# Top.net
KiCad netlist of a schematic drawn in Altium Designer
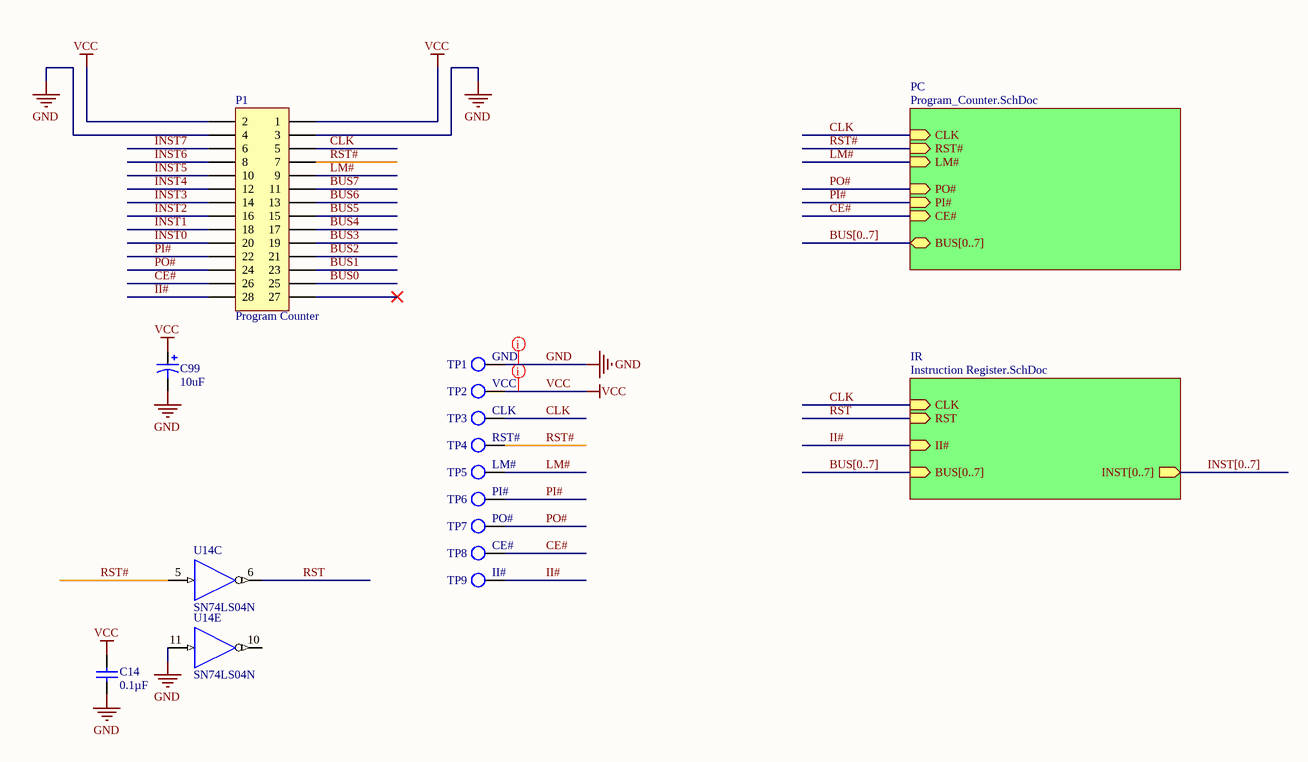
[diagram p0: Top.SchDoc]

(export (version "E")
  (design (tool "Eeschema 10.0.6"))
  (components
    (comp (ref "C14")
      (value "K104K15X7RF5TL2")
      (footprint "VISH-K104K15X7RF5TL2")
      (description "Ceramic Capacitor, 100 nF, +/- 10%, 50 V, -55 to 125 degC, 2-Pin THD, RoHS, Tape and Reel")
      (fields
        (field (name "MANUFACTURER") "Vishay")
        (field (name "TOLERANCE") "±10%")
        (field (name "CAPACITANCE") "0.1µF")
      )
      (libsource (lib "Altium Content Vault") (part "CAP-NP-2"))
    )
    (comp (ref "C99")
      (value "10uF")
      (footprint "C5x7")
      (description "Polarized Capacitor")
      (fields (field (name "Comment") "Cap Pol5") (field (name "PUBLISHER") "Altium Limited"))
      (libsource (lib "Miscellaneous Devices") (part "Cap Pol5"))
    )
    (comp (ref "P1")
      (value "Program Counter")
      (footprint "HDR2X14H")
      (description "Header, 14-Pin, Dual row, Right Angle")
      (fields (field (name "PUBLISHER") "Altium Limited"))
      (libsource (lib "Miscellaneous Connectors") (part "Header 14X2H"))
    )
    (comp (ref "TP1") (value "GND") (footprint "KSTN-5011_V") (libsource (lib "TP") (part "TP")))
    (comp (ref "TP2") (value "VCC") (footprint "KSTN-5011_V") (libsource (lib "TP") (part "TP")))
    (comp (ref "TP3") (value "CLK") (footprint "KSTN-5011_V") (libsource (lib "TP") (part "TP")))
    (comp (ref "TP4") (value "RST#") (footprint "KSTN-5011_V") (libsource (lib "TP") (part "TP")))
    (comp (ref "TP5") (value "LM#") (footprint "KSTN-5011_V") (libsource (lib "TP") (part "TP")))
    (comp (ref "TP6") (value "PI#") (footprint "KSTN-5011_V") (libsource (lib "TP") (part "TP")))
    (comp (ref "TP7") (value "PO#") (footprint "KSTN-5011_V") (libsource (lib "TP") (part "TP")))
    (comp (ref "TP8") (value "CE#") (footprint "KSTN-5011_V") (libsource (lib "TP") (part "TP")))
    (comp (ref "TP9") (value "II#") (footprint "KSTN-5011_V") (libsource (lib "TP") (part "TP")))
    (comp (ref "U14")
      (value "SN74LS04N")
      (footprint "N014")
      (description "Hex Inverter")
      (fields (field (name "PUBLISHER") "Altium Limited"))
      (libsource (lib "TI Logic Gate 2") (part "SN74LS04N"))
    )
  )
  (nets
    (net (code "1") (name "/BUS0") (class "Default")
      (node (ref "P1") (pin "25") (pinfunction "25_25") (pintype "passive"))
    )
    (net (code "2") (name "/BUS1") (class "Default")
      (node (ref "P1") (pin "23") (pinfunction "23_23") (pintype "passive"))
    )
    (net (code "3") (name "/BUS2") (class "Default")
      (node (ref "P1") (pin "21") (pinfunction "21_21") (pintype "passive"))
    )
    (net (code "4") (name "/BUS3") (class "Default")
      (node (ref "P1") (pin "19") (pinfunction "19_19") (pintype "passive"))
    )
    (net (code "5") (name "/BUS4") (class "Default")
      (node (ref "P1") (pin "17") (pinfunction "17_17") (pintype "passive"))
    )
    (net (code "6") (name "/BUS5") (class "Default")
      (node (ref "P1") (pin "15") (pinfunction "15_15") (pintype "passive"))
    )
    (net (code "7") (name "/BUS6") (class "Default")
      (node (ref "P1") (pin "13") (pinfunction "13_13") (pintype "passive"))
    )
    (net (code "8") (name "/BUS7") (class "Default")
      (node (ref "P1") (pin "11") (pinfunction "11_11") (pintype "passive"))
    )
    (net (code "10") (name "/CE#") (class "Default")
      (node (ref "P1") (pin "26") (pinfunction "26_26") (pintype "passive"))
      (node (ref "TP8") (pin "1") (pintype "passive"))
    )
    (net (code "11") (name "/CLK") (class "Default")
      (node (ref "P1") (pin "5") (pinfunction "5_5") (pintype "passive"))
      (node (ref "TP3") (pin "1") (pintype "passive"))
    )
    (net (code "12") (name "/II#") (class "Default")
      (node (ref "P1") (pin "28") (pinfunction "28_28") (pintype "passive"))
      (node (ref "TP9") (pin "1") (pintype "passive"))
    )
    (net (code "13") (name "/INST0") (class "Default")
      (node (ref "P1") (pin "20") (pinfunction "20_20") (pintype "passive"))
    )
    (net (code "14") (name "/INST1") (class "Default")
      (node (ref "P1") (pin "18") (pinfunction "18_18") (pintype "passive"))
    )
    (net (code "15") (name "/INST2") (class "Default")
      (node (ref "P1") (pin "16") (pinfunction "16_16") (pintype "passive"))
    )
    (net (code "16") (name "/INST3") (class "Default")
      (node (ref "P1") (pin "14") (pinfunction "14_14") (pintype "passive"))
    )
    (net (code "17") (name "/INST4") (class "Default")
      (node (ref "P1") (pin "12") (pinfunction "12_12") (pintype "passive"))
    )
    (net (code "18") (name "/INST5") (class "Default")
      (node (ref "P1") (pin "10") (pinfunction "10_10") (pintype "passive"))
    )
    (net (code "19") (name "/INST6") (class "Default")
      (node (ref "P1") (pin "8") (pinfunction "8_8") (pintype "passive"))
    )
    (net (code "20") (name "/INST7") (class "Default")
      (node (ref "P1") (pin "6") (pinfunction "6_6") (pintype "passive"))
    )
    (net (code "22") (name "/LM#") (class "Default")
      (node (ref "P1") (pin "9") (pinfunction "9_9") (pintype "passive"))
      (node (ref "TP5") (pin "1") (pintype "passive"))
    )
    (net (code "23") (name "/PI#") (class "Default")
      (node (ref "P1") (pin "22") (pinfunction "22_22") (pintype "passive"))
      (node (ref "TP6") (pin "1") (pintype "passive"))
    )
    (net (code "24") (name "/PO#") (class "Default")
      (node (ref "P1") (pin "24") (pinfunction "24_24") (pintype "passive"))
      (node (ref "TP7") (pin "1") (pintype "passive"))
    )
    (net (code "25") (name "/RST") (class "Default")
      (node (ref "U14") (pin "6") (pinfunction "Y_6") (pintype "output"))
    )
    (net (code "26") (name "/RST#") (class "Default")
      (node (ref "P1") (pin "7") (pinfunction "7_7") (pintype "passive"))
      (node (ref "TP4") (pin "1") (pintype "passive"))
      (node (ref "U14") (pin "5") (pinfunction "A_5") (pintype "input"))
    )
    (net (code "27") (name "GND") (class "Default")
      (node (ref "C14") (pin "2") (pinfunction "2_2") (pintype "passive"))
      (node (ref "C99") (pin "2") (pinfunction "2_2") (pintype "passive"))
      (node (ref "P1") (pin "3") (pinfunction "3_3") (pintype "passive"))
      (node (ref "P1") (pin "4") (pinfunction "4_4") (pintype "passive"))
      (node (ref "TP1") (pin "1") (pintype "passive"))
      (node (ref "U14") (pin "11") (pinfunction "A_11") (pintype "input"))
      (node (ref "U14") (pin "7") (pinfunction "GND_7") (pintype "power_in"))
    )
    (net (code "28") (name "VCC") (class "Default")
      (node (ref "C14") (pin "1") (pinfunction "1_1") (pintype "passive"))
      (node (ref "C99") (pin "1") (pinfunction "1_1") (pintype "passive"))
      (node (ref "P1") (pin "1") (pinfunction "1_1") (pintype "passive"))
      (node (ref "P1") (pin "2") (pinfunction "2_2") (pintype "passive"))
      (node (ref "TP2") (pin "1") (pintype "passive"))
      (node (ref "U14") (pin "14") (pinfunction "VCC_14") (pintype "power_in"))
    )
    (net (code "29") (name "unconnected-(P1-Pad27)") (class "Default")
      (node (ref "P1") (pin "27") (pinfunction "27_27") (pintype "passive+no_connect"))
    )
    (net (code "30") (name "unconnected-(U14E-Y-Pad10)") (class "Default")
      (node (ref "U14") (pin "10") (pinfunction "Y_10") (pintype "output"))
    )
  )
)
